# differentiator.net
KiCad netlist of a schematic drawn in EAGLE
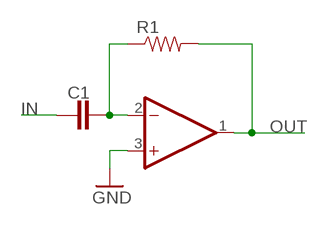
[diagram p0: schematic, sheet 1]

(export (version "E")
  (design (tool "Eeschema 10.0.6"))
  (components
    (comp (ref "C1")
      (value "CAP0402-CAP")
      (footprint "eagle-import:0402-CAP")
      (libsource (lib "eagle-import") (part "CAP0402-CAP"))
    )
    (comp (ref "IC1")
      (value "MCP6022")
      (footprint "eagle-import:SOIC8_150MIL")
      (libsource (lib "eagle-import") (part "MCP6022"))
    )
    (comp (ref "R1")
      (value "RESISTOR0402-RES")
      (footprint "eagle-import:0402-RES")
      (libsource (lib "eagle-import") (part "RESISTOR0402-RES"))
    )
  )
  (nets
    (net (code "1") (name "/IN") (class "Default")
      (node (ref "C1") (pin "1") (pinfunction "1_1") (pintype "passive"))
    )
    (net (code "2") (name "/OUT") (class "Default")
      (node (ref "IC1") (pin "1") (pinfunction "OUT_1") (pintype "output"))
      (node (ref "R1") (pin "2") (pinfunction "2_2") (pintype "passive"))
    )
    (net (code "3") (name "GND") (class "Default")
      (node (ref "IC1") (pin "3") (pinfunction "+IN_3") (pintype "input"))
    )
    (net (code "4") (name "Net-(IC1A--IN)") (class "Default")
      (node (ref "C1") (pin "2") (pinfunction "2_2") (pintype "passive"))
      (node (ref "IC1") (pin "2") (pinfunction "-IN_2") (pintype "input"))
      (node (ref "R1") (pin "1") (pinfunction "1_1") (pintype "passive"))
    )
  )
)
